# S3_LED_MAT_FPGA_POWER.net
KiCad netlist of a schematic drawn in Altium Designer
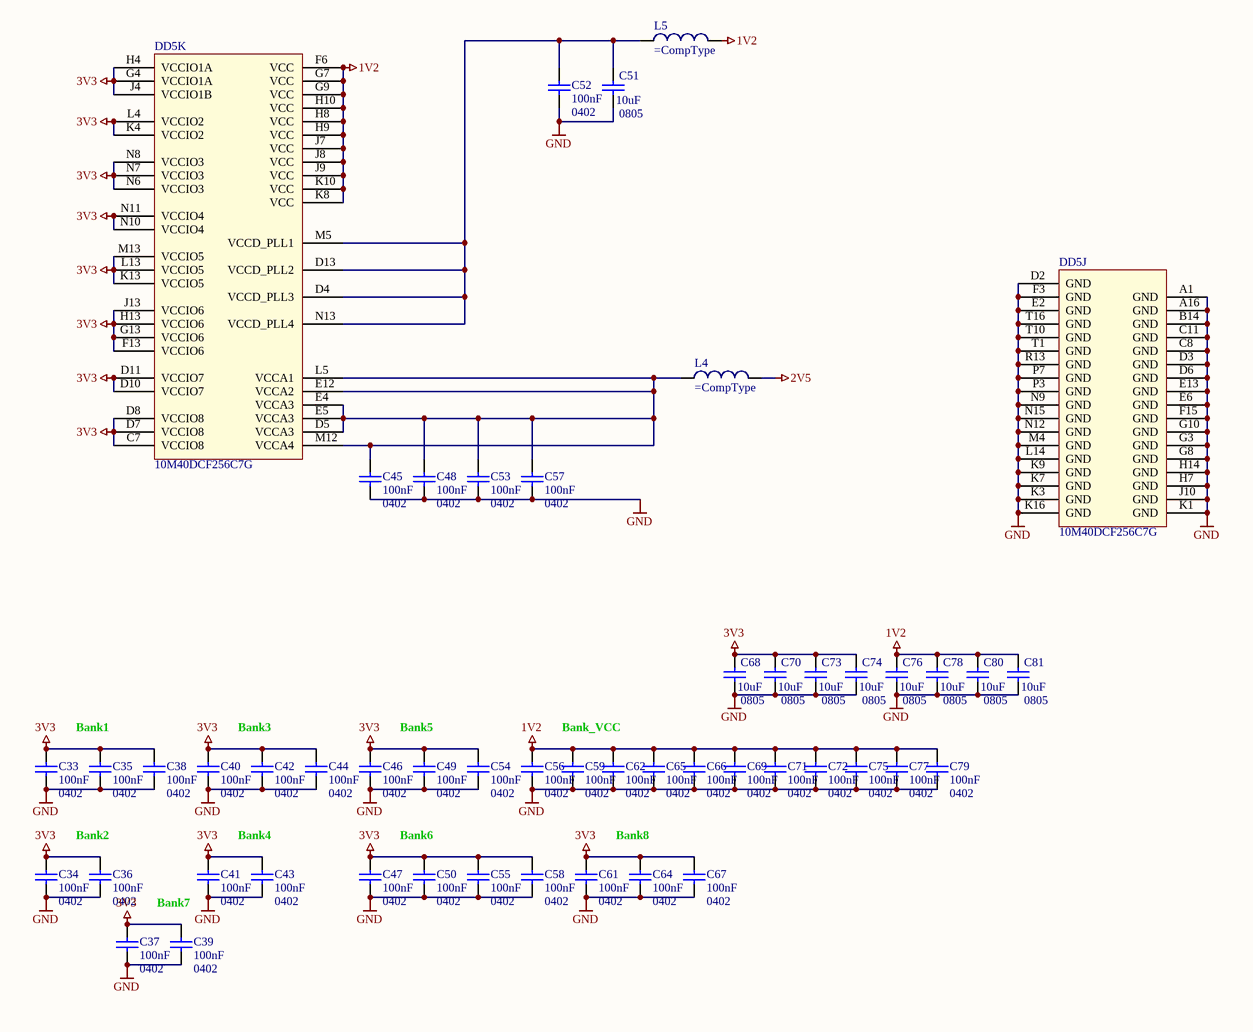
[diagram p0: S3_LED_MAT_FPGA_POWER.SchDoc]

(export (version "E")
  (design (tool "Eeschema 10.0.6"))
  (components
    (comp (ref "C33")
      (value "100nF")
      (footprint "CAPC1005L")
      (description "Capacitor ceramic")
      (fields
        (field (name "MANUFACTURER") "SAMSUNG")
        (field (name "MANUFACTURER PART NUMBER") "CL05B104KO5NNNC")
        (field (name "PACKAGE") "0402")
      )
      (libsource (lib "LED_MAT_3") (part "100nF / 0402 / X7R / 16V"))
    )
    (comp (ref "C34")
      (value "100nF")
      (footprint "CAPC1005L")
      (description "Capacitor ceramic")
      (fields
        (field (name "MANUFACTURER") "SAMSUNG")
        (field (name "MANUFACTURER PART NUMBER") "CL05B104KO5NNNC")
        (field (name "PACKAGE") "0402")
      )
      (libsource (lib "LED_MAT_3") (part "100nF / 0402 / X7R / 16V"))
    )
    (comp (ref "C35")
      (value "100nF")
      (footprint "CAPC1005L")
      (description "Capacitor ceramic")
      (fields
        (field (name "MANUFACTURER") "SAMSUNG")
        (field (name "MANUFACTURER PART NUMBER") "CL05B104KO5NNNC")
        (field (name "PACKAGE") "0402")
      )
      (libsource (lib "LED_MAT_3") (part "100nF / 0402 / X7R / 16V"))
    )
    (comp (ref "C36")
      (value "100nF")
      (footprint "CAPC1005L")
      (description "Capacitor ceramic")
      (fields
        (field (name "MANUFACTURER") "SAMSUNG")
        (field (name "MANUFACTURER PART NUMBER") "CL05B104KO5NNNC")
        (field (name "PACKAGE") "0402")
      )
      (libsource (lib "LED_MAT_3") (part "100nF / 0402 / X7R / 16V"))
    )
    (comp (ref "C37")
      (value "100nF")
      (footprint "CAPC1005L")
      (description "Capacitor ceramic")
      (fields
        (field (name "MANUFACTURER") "SAMSUNG")
        (field (name "MANUFACTURER PART NUMBER") "CL05B104KO5NNNC")
        (field (name "PACKAGE") "0402")
      )
      (libsource (lib "LED_MAT_3") (part "100nF / 0402 / X7R / 16V"))
    )
    (comp (ref "C38")
      (value "100nF")
      (footprint "CAPC1005L")
      (description "Capacitor ceramic")
      (fields
        (field (name "MANUFACTURER") "SAMSUNG")
        (field (name "MANUFACTURER PART NUMBER") "CL05B104KO5NNNC")
        (field (name "PACKAGE") "0402")
      )
      (libsource (lib "LED_MAT_3") (part "100nF / 0402 / X7R / 16V"))
    )
    (comp (ref "C39")
      (value "100nF")
      (footprint "CAPC1005L")
      (description "Capacitor ceramic")
      (fields
        (field (name "MANUFACTURER") "SAMSUNG")
        (field (name "MANUFACTURER PART NUMBER") "CL05B104KO5NNNC")
        (field (name "PACKAGE") "0402")
      )
      (libsource (lib "LED_MAT_3") (part "100nF / 0402 / X7R / 16V"))
    )
    (comp (ref "C40")
      (value "100nF")
      (footprint "CAPC1005L")
      (description "Capacitor ceramic")
      (fields
        (field (name "MANUFACTURER") "SAMSUNG")
        (field (name "MANUFACTURER PART NUMBER") "CL05B104KO5NNNC")
        (field (name "PACKAGE") "0402")
      )
      (libsource (lib "LED_MAT_3") (part "100nF / 0402 / X7R / 16V"))
    )
    (comp (ref "C41")
      (value "100nF")
      (footprint "CAPC1005L")
      (description "Capacitor ceramic")
      (fields
        (field (name "MANUFACTURER") "SAMSUNG")
        (field (name "MANUFACTURER PART NUMBER") "CL05B104KO5NNNC")
        (field (name "PACKAGE") "0402")
      )
      (libsource (lib "LED_MAT_3") (part "100nF / 0402 / X7R / 16V"))
    )
    (comp (ref "C42")
      (value "100nF")
      (footprint "CAPC1005L")
      (description "Capacitor ceramic")
      (fields
        (field (name "MANUFACTURER") "SAMSUNG")
        (field (name "MANUFACTURER PART NUMBER") "CL05B104KO5NNNC")
        (field (name "PACKAGE") "0402")
      )
      (libsource (lib "LED_MAT_3") (part "100nF / 0402 / X7R / 16V"))
    )
    (comp (ref "C43")
      (value "100nF")
      (footprint "CAPC1005L")
      (description "Capacitor ceramic")
      (fields
        (field (name "MANUFACTURER") "SAMSUNG")
        (field (name "MANUFACTURER PART NUMBER") "CL05B104KO5NNNC")
        (field (name "PACKAGE") "0402")
      )
      (libsource (lib "LED_MAT_3") (part "100nF / 0402 / X7R / 16V"))
    )
    (comp (ref "C44")
      (value "100nF")
      (footprint "CAPC1005L")
      (description "Capacitor ceramic")
      (fields
        (field (name "MANUFACTURER") "SAMSUNG")
        (field (name "MANUFACTURER PART NUMBER") "CL05B104KO5NNNC")
        (field (name "PACKAGE") "0402")
      )
      (libsource (lib "LED_MAT_3") (part "100nF / 0402 / X7R / 16V"))
    )
    (comp (ref "C45")
      (value "100nF")
      (footprint "CAPC1005L")
      (description "Capacitor ceramic")
      (fields
        (field (name "MANUFACTURER") "SAMSUNG")
        (field (name "MANUFACTURER PART NUMBER") "CL05B104KO5NNNC")
        (field (name "PACKAGE") "0402")
      )
      (libsource (lib "LED_MAT_3") (part "100nF / 0402 / X7R / 16V"))
    )
    (comp (ref "C46")
      (value "100nF")
      (footprint "CAPC1005L")
      (description "Capacitor ceramic")
      (fields
        (field (name "MANUFACTURER") "SAMSUNG")
        (field (name "MANUFACTURER PART NUMBER") "CL05B104KO5NNNC")
        (field (name "PACKAGE") "0402")
      )
      (libsource (lib "LED_MAT_3") (part "100nF / 0402 / X7R / 16V"))
    )
    (comp (ref "C47")
      (value "100nF")
      (footprint "CAPC1005L")
      (description "Capacitor ceramic")
      (fields
        (field (name "MANUFACTURER") "SAMSUNG")
        (field (name "MANUFACTURER PART NUMBER") "CL05B104KO5NNNC")
        (field (name "PACKAGE") "0402")
      )
      (libsource (lib "LED_MAT_3") (part "100nF / 0402 / X7R / 16V"))
    )
    (comp (ref "C48")
      (value "100nF")
      (footprint "CAPC1005L")
      (description "Capacitor ceramic")
      (fields
        (field (name "MANUFACTURER") "SAMSUNG")
        (field (name "MANUFACTURER PART NUMBER") "CL05B104KO5NNNC")
        (field (name "PACKAGE") "0402")
      )
      (libsource (lib "LED_MAT_3") (part "100nF / 0402 / X7R / 16V"))
    )
    (comp (ref "C49")
      (value "100nF")
      (footprint "CAPC1005L")
      (description "Capacitor ceramic")
      (fields
        (field (name "MANUFACTURER") "SAMSUNG")
        (field (name "MANUFACTURER PART NUMBER") "CL05B104KO5NNNC")
        (field (name "PACKAGE") "0402")
      )
      (libsource (lib "LED_MAT_3") (part "100nF / 0402 / X7R / 16V"))
    )
    (comp (ref "C50")
      (value "100nF")
      (footprint "CAPC1005L")
      (description "Capacitor ceramic")
      (fields
        (field (name "MANUFACTURER") "SAMSUNG")
        (field (name "MANUFACTURER PART NUMBER") "CL05B104KO5NNNC")
        (field (name "PACKAGE") "0402")
      )
      (libsource (lib "LED_MAT_3") (part "100nF / 0402 / X7R / 16V"))
    )
    (comp (ref "C51")
      (value "10uF")
      (footprint "CAPC2012L")
      (description "Capacitor ceramic")
      (fields
        (field (name "PACKAGE") "0805")
        (field (name "VOLTAGE") "10V")
        (field (name "Comment") "10uF / 0805 /  X5R / 10V")
      )
      (libsource (lib "LED_MAT_3") (part "10uF / 0805 /  X5R / 10V"))
    )
    (comp (ref "C52")
      (value "100nF")
      (footprint "CAPC1005L")
      (description "Capacitor ceramic")
      (fields
        (field (name "MANUFACTURER") "SAMSUNG")
        (field (name "MANUFACTURER PART NUMBER") "CL05B104KO5NNNC")
        (field (name "PACKAGE") "0402")
      )
      (libsource (lib "LED_MAT_3") (part "100nF / 0402 / X7R / 16V"))
    )
    (comp (ref "C53")
      (value "100nF")
      (footprint "CAPC1005L")
      (description "Capacitor ceramic")
      (fields
        (field (name "MANUFACTURER") "SAMSUNG")
        (field (name "MANUFACTURER PART NUMBER") "CL05B104KO5NNNC")
        (field (name "PACKAGE") "0402")
      )
      (libsource (lib "LED_MAT_3") (part "100nF / 0402 / X7R / 16V"))
    )
    (comp (ref "C54")
      (value "100nF")
      (footprint "CAPC1005L")
      (description "Capacitor ceramic")
      (fields
        (field (name "MANUFACTURER") "SAMSUNG")
        (field (name "MANUFACTURER PART NUMBER") "CL05B104KO5NNNC")
        (field (name "PACKAGE") "0402")
      )
      (libsource (lib "LED_MAT_3") (part "100nF / 0402 / X7R / 16V"))
    )
    (comp (ref "C55")
      (value "100nF")
      (footprint "CAPC1005L")
      (description "Capacitor ceramic")
      (fields
        (field (name "MANUFACTURER") "SAMSUNG")
        (field (name "MANUFACTURER PART NUMBER") "CL05B104KO5NNNC")
        (field (name "PACKAGE") "0402")
      )
      (libsource (lib "LED_MAT_3") (part "100nF / 0402 / X7R / 16V"))
    )
    (comp (ref "C56")
      (value "100nF")
      (footprint "CAPC1005L")
      (description "Capacitor ceramic")
      (fields
        (field (name "MANUFACTURER") "SAMSUNG")
        (field (name "MANUFACTURER PART NUMBER") "CL05B104KO5NNNC")
        (field (name "PACKAGE") "0402")
      )
      (libsource (lib "LED_MAT_3") (part "100nF / 0402 / X7R / 16V"))
    )
    (comp (ref "C57")
      (value "100nF")
      (footprint "CAPC1005L")
      (description "Capacitor ceramic")
      (fields
        (field (name "MANUFACTURER") "SAMSUNG")
        (field (name "MANUFACTURER PART NUMBER") "CL05B104KO5NNNC")
        (field (name "PACKAGE") "0402")
      )
      (libsource (lib "LED_MAT_3") (part "100nF / 0402 / X7R / 16V"))
    )
    (comp (ref "C58")
      (value "100nF")
      (footprint "CAPC1005L")
      (description "Capacitor ceramic")
      (fields
        (field (name "MANUFACTURER") "SAMSUNG")
        (field (name "MANUFACTURER PART NUMBER") "CL05B104KO5NNNC")
        (field (name "PACKAGE") "0402")
      )
      (libsource (lib "LED_MAT_3") (part "100nF / 0402 / X7R / 16V"))
    )
    (comp (ref "C59")
      (value "100nF")
      (footprint "CAPC1005L")
      (description "Capacitor ceramic")
      (fields
        (field (name "MANUFACTURER") "SAMSUNG")
        (field (name "MANUFACTURER PART NUMBER") "CL05B104KO5NNNC")
        (field (name "PACKAGE") "0402")
      )
      (libsource (lib "LED_MAT_3") (part "100nF / 0402 / X7R / 16V"))
    )
    (comp (ref "C61")
      (value "100nF")
      (footprint "CAPC1005L")
      (description "Capacitor ceramic")
      (fields
        (field (name "MANUFACTURER") "SAMSUNG")
        (field (name "MANUFACTURER PART NUMBER") "CL05B104KO5NNNC")
        (field (name "PACKAGE") "0402")
      )
      (libsource (lib "LED_MAT_3") (part "100nF / 0402 / X7R / 16V"))
    )
    (comp (ref "C62")
      (value "100nF")
      (footprint "CAPC1005L")
      (description "Capacitor ceramic")
      (fields
        (field (name "MANUFACTURER") "SAMSUNG")
        (field (name "MANUFACTURER PART NUMBER") "CL05B104KO5NNNC")
        (field (name "PACKAGE") "0402")
      )
      (libsource (lib "LED_MAT_3") (part "100nF / 0402 / X7R / 16V"))
    )
    (comp (ref "C64")
      (value "100nF")
      (footprint "CAPC1005L")
      (description "Capacitor ceramic")
      (fields
        (field (name "MANUFACTURER") "SAMSUNG")
        (field (name "MANUFACTURER PART NUMBER") "CL05B104KO5NNNC")
        (field (name "PACKAGE") "0402")
      )
      (libsource (lib "LED_MAT_3") (part "100nF / 0402 / X7R / 16V"))
    )
    (comp (ref "C65")
      (value "100nF")
      (footprint "CAPC1005L")
      (description "Capacitor ceramic")
      (fields
        (field (name "MANUFACTURER") "SAMSUNG")
        (field (name "MANUFACTURER PART NUMBER") "CL05B104KO5NNNC")
        (field (name "PACKAGE") "0402")
      )
      (libsource (lib "LED_MAT_3") (part "100nF / 0402 / X7R / 16V"))
    )
    (comp (ref "C66")
      (value "100nF")
      (footprint "CAPC1005L")
      (description "Capacitor ceramic")
      (fields
        (field (name "MANUFACTURER") "SAMSUNG")
        (field (name "MANUFACTURER PART NUMBER") "CL05B104KO5NNNC")
        (field (name "PACKAGE") "0402")
      )
      (libsource (lib "LED_MAT_3") (part "100nF / 0402 / X7R / 16V"))
    )
    (comp (ref "C67")
      (value "100nF")
      (footprint "CAPC1005L")
      (description "Capacitor ceramic")
      (fields
        (field (name "MANUFACTURER") "SAMSUNG")
        (field (name "MANUFACTURER PART NUMBER") "CL05B104KO5NNNC")
        (field (name "PACKAGE") "0402")
      )
      (libsource (lib "LED_MAT_3") (part "100nF / 0402 / X7R / 16V"))
    )
    (comp (ref "C68")
      (value "10uF")
      (footprint "CAPC2012L")
      (description "Capacitor ceramic")
      (fields
        (field (name "PACKAGE") "0805")
        (field (name "VOLTAGE") "10V")
        (field (name "Comment") "10uF / 0805 /  X5R / 10V")
      )
      (libsource (lib "LED_MAT_3") (part "10uF / 0805 /  X5R / 10V"))
    )
    (comp (ref "C69")
      (value "100nF")
      (footprint "CAPC1005L")
      (description "Capacitor ceramic")
      (fields
        (field (name "MANUFACTURER") "SAMSUNG")
        (field (name "MANUFACTURER PART NUMBER") "CL05B104KO5NNNC")
        (field (name "PACKAGE") "0402")
      )
      (libsource (lib "LED_MAT_3") (part "100nF / 0402 / X7R / 16V"))
    )
    (comp (ref "C70")
      (value "10uF")
      (footprint "CAPC2012L")
      (description "Capacitor ceramic")
      (fields
        (field (name "PACKAGE") "0805")
        (field (name "VOLTAGE") "10V")
        (field (name "Comment") "10uF / 0805 /  X5R / 10V")
      )
      (libsource (lib "LED_MAT_3") (part "10uF / 0805 /  X5R / 10V"))
    )
    (comp (ref "C71")
      (value "100nF")
      (footprint "CAPC1005L")
      (description "Capacitor ceramic")
      (fields
        (field (name "MANUFACTURER") "SAMSUNG")
        (field (name "MANUFACTURER PART NUMBER") "CL05B104KO5NNNC")
        (field (name "PACKAGE") "0402")
      )
      (libsource (lib "LED_MAT_3") (part "100nF / 0402 / X7R / 16V"))
    )
    (comp (ref "C72")
      (value "100nF")
      (footprint "CAPC1005L")
      (description "Capacitor ceramic")
      (fields
        (field (name "MANUFACTURER") "SAMSUNG")
        (field (name "MANUFACTURER PART NUMBER") "CL05B104KO5NNNC")
        (field (name "PACKAGE") "0402")
      )
      (libsource (lib "LED_MAT_3") (part "100nF / 0402 / X7R / 16V"))
    )
    (comp (ref "C73")
      (value "10uF")
      (footprint "CAPC2012L")
      (description "Capacitor ceramic")
      (fields
        (field (name "PACKAGE") "0805")
        (field (name "VOLTAGE") "10V")
        (field (name "Comment") "10uF / 0805 /  X5R / 10V")
      )
      (libsource (lib "LED_MAT_3") (part "10uF / 0805 /  X5R / 10V"))
    )
    (comp (ref "C74")
      (value "10uF")
      (footprint "CAPC2012L")
      (description "Capacitor ceramic")
      (fields
        (field (name "PACKAGE") "0805")
        (field (name "VOLTAGE") "10V")
        (field (name "Comment") "10uF / 0805 /  X5R / 10V")
      )
      (libsource (lib "LED_MAT_3") (part "10uF / 0805 /  X5R / 10V"))
    )
    (comp (ref "C75")
      (value "100nF")
      (footprint "CAPC1005L")
      (description "Capacitor ceramic")
      (fields
        (field (name "MANUFACTURER") "SAMSUNG")
        (field (name "MANUFACTURER PART NUMBER") "CL05B104KO5NNNC")
        (field (name "PACKAGE") "0402")
      )
      (libsource (lib "LED_MAT_3") (part "100nF / 0402 / X7R / 16V"))
    )
    (comp (ref "C76")
      (value "10uF")
      (footprint "CAPC2012L")
      (description "Capacitor ceramic")
      (fields
        (field (name "PACKAGE") "0805")
        (field (name "VOLTAGE") "10V")
        (field (name "Comment") "10uF / 0805 /  X5R / 10V")
      )
      (libsource (lib "LED_MAT_3") (part "10uF / 0805 /  X5R / 10V"))
    )
    (comp (ref "C77")
      (value "100nF")
      (footprint "CAPC1005L")
      (description "Capacitor ceramic")
      (fields
        (field (name "MANUFACTURER") "SAMSUNG")
        (field (name "MANUFACTURER PART NUMBER") "CL05B104KO5NNNC")
        (field (name "PACKAGE") "0402")
      )
      (libsource (lib "LED_MAT_3") (part "100nF / 0402 / X7R / 16V"))
    )
    (comp (ref "C78")
      (value "10uF")
      (footprint "CAPC2012L")
      (description "Capacitor ceramic")
      (fields
        (field (name "PACKAGE") "0805")
        (field (name "VOLTAGE") "10V")
        (field (name "Comment") "10uF / 0805 /  X5R / 10V")
      )
      (libsource (lib "LED_MAT_3") (part "10uF / 0805 /  X5R / 10V"))
    )
    (comp (ref "C79")
      (value "100nF")
      (footprint "CAPC1005L")
      (description "Capacitor ceramic")
      (fields
        (field (name "MANUFACTURER") "SAMSUNG")
        (field (name "MANUFACTURER PART NUMBER") "CL05B104KO5NNNC")
        (field (name "PACKAGE") "0402")
      )
      (libsource (lib "LED_MAT_3") (part "100nF / 0402 / X7R / 16V"))
    )
    (comp (ref "C80")
      (value "10uF")
      (footprint "CAPC2012L")
      (description "Capacitor ceramic")
      (fields
        (field (name "PACKAGE") "0805")
        (field (name "VOLTAGE") "10V")
        (field (name "Comment") "10uF / 0805 /  X5R / 10V")
      )
      (libsource (lib "LED_MAT_3") (part "10uF / 0805 /  X5R / 10V"))
    )
    (comp (ref "C81")
      (value "10uF")
      (footprint "CAPC2012L")
      (description "Capacitor ceramic")
      (fields
        (field (name "PACKAGE") "0805")
        (field (name "VOLTAGE") "10V")
        (field (name "Comment") "10uF / 0805 /  X5R / 10V")
      )
      (libsource (lib "LED_MAT_3") (part "10uF / 0805 /  X5R / 10V"))
    )
    (comp (ref "DD5")
      (value "10M40DCF256C7G")
      (footprint "BGA100P16X16-256")
      (description "FPGA")
      (fields
        (field (name "MANUFACTURER") "ALTERA")
        (field (name "MANUFACTURER PART NUMBER") "10M40DCF256C7GA")
      )
      (libsource (lib "IC") (part "10M40DCF256C7G"))
    )
    (comp (ref "L4")
      (value "~")
      (footprint "INDC2012L")
      (description "Ferrite bead")
      (fields
        (field (name "MANUFACTURER") "Murata")
        (field (name "MANUFACTURER PART NUMBER") "BLM21PG221SN1")
      )
      (libsource (lib "LED_MAT_3") (part "INDUCTOR"))
    )
    (comp (ref "L5")
      (value "~")
      (footprint "INDC2012L")
      (description "Ferrite bead")
      (fields
        (field (name "MANUFACTURER") "Murata")
        (field (name "MANUFACTURER PART NUMBER") "BLM21PG221SN1")
      )
      (libsource (lib "LED_MAT_3") (part "INDUCTOR"))
    )
  )
  (nets
    (net (code "1") (name "1V2") (class "Default")
      (node (ref "C56") (pin "2") (pinfunction "2_2") (pintype "passive"))
      (node (ref "C59") (pin "2") (pinfunction "2_2") (pintype "passive"))
      (node (ref "C62") (pin "2") (pinfunction "2_2") (pintype "passive"))
      (node (ref "C65") (pin "2") (pinfunction "2_2") (pintype "passive"))
      (node (ref "C66") (pin "2") (pinfunction "2_2") (pintype "passive"))
      (node (ref "C69") (pin "2") (pinfunction "2_2") (pintype "passive"))
      (node (ref "C71") (pin "2") (pinfunction "2_2") (pintype "passive"))
      (node (ref "C72") (pin "2") (pinfunction "2_2") (pintype "passive"))
      (node (ref "C75") (pin "2") (pinfunction "2_2") (pintype "passive"))
      (node (ref "C76") (pin "2") (pinfunction "2_2") (pintype "passive"))
      (node (ref "C77") (pin "2") (pinfunction "2_2") (pintype "passive"))
      (node (ref "C78") (pin "2") (pinfunction "2_2") (pintype "passive"))
      (node (ref "C79") (pin "2") (pinfunction "2_2") (pintype "passive"))
      (node (ref "C80") (pin "2") (pinfunction "2_2") (pintype "passive"))
      (node (ref "C81") (pin "2") (pinfunction "2_2") (pintype "passive"))
      (node (ref "DD5") (pin "F6") (pinfunction "VCC_F6") (pintype "power_in"))
      (node (ref "DD5") (pin "G7") (pinfunction "VCC_G7") (pintype "power_in"))
      (node (ref "DD5") (pin "G9") (pinfunction "VCC_G9") (pintype "power_in"))
      (node (ref "DD5") (pin "H10") (pinfunction "VCC_H10") (pintype "power_in"))
      (node (ref "DD5") (pin "H8") (pinfunction "VCC_H8") (pintype "power_in"))
      (node (ref "DD5") (pin "H9") (pinfunction "VCC_H9") (pintype "power_in"))
      (node (ref "DD5") (pin "J7") (pinfunction "VCC_J7") (pintype "power_in"))
      (node (ref "DD5") (pin "J8") (pinfunction "VCC_J8") (pintype "power_in"))
      (node (ref "DD5") (pin "J9") (pinfunction "VCC_J9") (pintype "power_in"))
      (node (ref "DD5") (pin "K10") (pinfunction "VCC_K10") (pintype "power_in"))
      (node (ref "DD5") (pin "K8") (pinfunction "VCC_K8") (pintype "power_in"))
      (node (ref "L5") (pin "2") (pinfunction "2_2") (pintype "passive"))
    )
    (net (code "2") (name "2V5") (class "Default")
      (node (ref "L4") (pin "2") (pinfunction "2_2") (pintype "passive"))
    )
    (net (code "3") (name "3V3") (class "Default")
      (node (ref "C33") (pin "2") (pinfunction "2_2") (pintype "passive"))
      (node (ref "C34") (pin "2") (pinfunction "2_2") (pintype "passive"))
      (node (ref "C35") (pin "2") (pinfunction "2_2") (pintype "passive"))
      (node (ref "C36") (pin "2") (pinfunction "2_2") (pintype "passive"))
      (node (ref "C37") (pin "2") (pinfunction "2_2") (pintype "passive"))
      (node (ref "C38") (pin "2") (pinfunction "2_2") (pintype "passive"))
      (node (ref "C39") (pin "2") (pinfunction "2_2") (pintype "passive"))
      (node (ref "C40") (pin "2") (pinfunction "2_2") (pintype "passive"))
      (node (ref "C41") (pin "2") (pinfunction "2_2") (pintype "passive"))
      (node (ref "C42") (pin "2") (pinfunction "2_2") (pintype "passive"))
      (node (ref "C43") (pin "2") (pinfunction "2_2") (pintype "passive"))
      (node (ref "C44") (pin "2") (pinfunction "2_2") (pintype "passive"))
      (node (ref "C46") (pin "2") (pinfunction "2_2") (pintype "passive"))
      (node (ref "C47") (pin "2") (pinfunction "2_2") (pintype "passive"))
      (node (ref "C49") (pin "2") (pinfunction "2_2") (pintype "passive"))
      (node (ref "C50") (pin "2") (pinfunction "2_2") (pintype "passive"))
      (node (ref "C54") (pin "2") (pinfunction "2_2") (pintype "passive"))
      (node (ref "C55") (pin "2") (pinfunction "2_2") (pintype "passive"))
      (node (ref "C58") (pin "2") (pinfunction "2_2") (pintype "passive"))
      (node (ref "C61") (pin "2") (pinfunction "2_2") (pintype "passive"))
      (node (ref "C64") (pin "2") (pinfunction "2_2") (pintype "passive"))
      (node (ref "C67") (pin "2") (pinfunction "2_2") (pintype "passive"))
      (node (ref "C68") (pin "2") (pinfunction "2_2") (pintype "passive"))
      (node (ref "C70") (pin "2") (pinfunction "2_2") (pintype "passive"))
      (node (ref "C73") (pin "2") (pinfunction "2_2") (pintype "passive"))
      (node (ref "C74") (pin "2") (pinfunction "2_2") (pintype "passive"))
      (node (ref "DD5") (pin "C7") (pinfunction "VCCIO8_C7") (pintype "power_in"))
      (node (ref "DD5") (pin "D10") (pinfunction "VCCIO7_D10") (pintype "power_in"))
      (node (ref "DD5") (pin "D11") (pinfunction "VCCIO7_D11") (pintype "power_in"))
      (node (ref "DD5") (pin "D7") (pinfunction "VCCIO8_D7") (pintype "power_in"))
      (node (ref "DD5") (pin "D8") (pinfunction "VCCIO8_D8") (pintype "power_in"))
      (node (ref "DD5") (pin "F13") (pinfunction "VCCIO6_F13") (pintype "power_in"))
      (node (ref "DD5") (pin "G13") (pinfunction "VCCIO6_G13") (pintype "power_in"))
      (node (ref "DD5") (pin "G4") (pinfunction "VCCIO1A_G4") (pintype "power_in"))
      (node (ref "DD5") (pin "H13") (pinfunction "VCCIO6_H13") (pintype "power_in"))
      (node (ref "DD5") (pin "H4") (pinfunction "VCCIO1A_H4") (pintype "power_in"))
      (node (ref "DD5") (pin "J13") (pinfunction "VCCIO6_J13") (pintype "power_in"))
      (node (ref "DD5") (pin "J4") (pinfunction "VCCIO1B_J4") (pintype "power_in"))
      (node (ref "DD5") (pin "K13") (pinfunction "VCCIO5_K13") (pintype "power_in"))
      (node (ref "DD5") (pin "K4") (pinfunction "VCCIO2_K4") (pintype "power_in"))
      (node (ref "DD5") (pin "L13") (pinfunction "VCCIO5_L13") (pintype "power_in"))
      (node (ref "DD5") (pin "L4") (pinfunction "VCCIO2_L4") (pintype "power_in"))
      (node (ref "DD5") (pin "M13") (pinfunction "VCCIO5_M13") (pintype "power_in"))
      (node (ref "DD5") (pin "N10") (pinfunction "VCCIO4_N10") (pintype "power_in"))
      (node (ref "DD5") (pin "N11") (pinfunction "VCCIO4_N11") (pintype "power_in"))
      (node (ref "DD5") (pin "N6") (pinfunction "VCCIO3_N6") (pintype "power_in"))
      (node (ref "DD5") (pin "N7") (pinfunction "VCCIO3_N7") (pintype "power_in"))
      (node (ref "DD5") (pin "N8") (pinfunction "VCCIO3_N8") (pintype "power_in"))
    )
    (net (code "4") (name "GND") (class "Default")
      (node (ref "C33") (pin "1") (pinfunction "1_1") (pintype "passive"))
      (node (ref "C34") (pin "1") (pinfunction "1_1") (pintype "passive"))
      (node (ref "C35") (pin "1") (pinfunction "1_1") (pintype "passive"))
      (node (ref "C36") (pin "1") (pinfunction "1_1") (pintype "passive"))
      (node (ref "C37") (pin "1") (pinfunction "1_1") (pintype "passive"))
      (node (ref "C38") (pin "1") (pinfunction "1_1") (pintype "passive"))
      (node (ref "C39") (pin "1") (pinfunction "1_1") (pintype "passive"))
      (node (ref "C40") (pin "1") (pinfunction "1_1") (pintype "passive"))
      (node (ref "C41") (pin "1") (pinfunction "1_1") (pintype "passive"))
      (node (ref "C42") (pin "1") (pinfunction "1_1") (pintype "passive"))
      (node (ref "C43") (pin "1") (pinfunction "1_1") (pintype "passive"))
      (node (ref "C44") (pin "1") (pinfunction "1_1") (pintype "passive"))
      (node (ref "C45") (pin "1") (pinfunction "1_1") (pintype "passive"))
      (node (ref "C46") (pin "1") (pinfunction "1_1") (pintype "passive"))
      (node (ref "C47") (pin "1") (pinfunction "1_1") (pintype "passive"))
      (node (ref "C48") (pin "1") (pinfunction "1_1") (pintype "passive"))
      (node (ref "C49") (pin "1") (pinfunction "1_1") (pintype "passive"))
      (node (ref "C50") (pin "1") (pinfunction "1_1") (pintype "passive"))
      (node (ref "C51") (pin "1") (pinfunction "1_1") (pintype "passive"))
      (node (ref "C52") (pin "1") (pinfunction "1_1") (pintype "passive"))
      (node (ref "C53") (pin "1") (pinfunction "1_1") (pintype "passive"))
      (node (ref "C54") (pin "1") (pinfunction "1_1") (pintype "passive"))
      (node (ref "C55") (pin "1") (pinfunction "1_1") (pintype "passive"))
      (node (ref "C56") (pin "1") (pinfunction "1_1") (pintype "passive"))
      (node (ref "C57") (pin "1") (pinfunction "1_1") (pintype "passive"))
      (node (ref "C58") (pin "1") (pinfunction "1_1") (pintype "passive"))
      (node (ref "C59") (pin "1") (pinfunction "1_1") (pintype "passive"))
      (node (ref "C61") (pin "1") (pinfunction "1_1") (pintype "passive"))
      (node (ref "C62") (pin "1") (pinfunction "1_1") (pintype "passive"))
      (node (ref "C64") (pin "1") (pinfunction "1_1") (pintype "passive"))
      (node (ref "C65") (pin "1") (pinfunction "1_1") (pintype "passive"))
      (node (ref "C66") (pin "1") (pinfunction "1_1") (pintype "passive"))
      (node (ref "C67") (pin "1") (pinfunction "1_1") (pintype "passive"))
      (node (ref "C68") (pin "1") (pinfunction "1_1") (pintype "passive"))
      (node (ref "C69") (pin "1") (pinfunction "1_1") (pintype "passive"))
      (node (ref "C70") (pin "1") (pinfunction "1_1") (pintype "passive"))
      (node (ref "C71") (pin "1") (pinfunction "1_1") (pintype "passive"))
      (node (ref "C72") (pin "1") (pinfunction "1_1") (pintype "passive"))
      (node (ref "C73") (pin "1") (pinfunction "1_1") (pintype "passive"))
      (node (ref "C74") (pin "1") (pinfunction "1_1") (pintype "passive"))
      (node (ref "C75") (pin "1") (pinfunction "1_1") (pintype "passive"))
      (node (ref "C76") (pin "1") (pinfunction "1_1") (pintype "passive"))
      (node (ref "C77") (pin "1") (pinfunction "1_1") (pintype "passive"))
      (node (ref "C78") (pin "1") (pinfunction "1_1") (pintype "passive"))
      (node (ref "C79") (pin "1") (pinfunction "1_1") (pintype "passive"))
      (node (ref "C80") (pin "1") (pinfunction "1_1") (pintype "passive"))
      (node (ref "C81") (pin "1") (pinfunction "1_1") (pintype "passive"))
      (node (ref "DD5") (pin "A1") (pinfunction "GND_A1") (pintype "power_in"))
      (node (ref "DD5") (pin "A16") (pinfunction "GND_A16") (pintype "power_in"))
      (node (ref "DD5") (pin "B14") (pinfunction "GND_B14") (pintype "power_in"))
      (node (ref "DD5") (pin "C11") (pinfunction "GND_C11") (pintype "power_in"))
      (node (ref "DD5") (pin "C8") (pinfunction "GND_C8") (pintype "power_in"))
      (node (ref "DD5") (pin "D2") (pinfunction "GND_D2") (pintype "power_in"))
      (node (ref "DD5") (pin "D3") (pinfunction "GND_D3") (pintype "power_in"))
      (node (ref "DD5") (pin "D6") (pinfunction "GND_D6") (pintype "power_in"))
      (node (ref "DD5") (pin "E13") (pinfunction "GND_E13") (pintype "power_in"))
      (node (ref "DD5") (pin "E2") (pinfunction "GND_E2") (pintype "power_in"))
      (node (ref "DD5") (pin "E6") (pinfunction "GND_E6") (pintype "power_in"))
      (node (ref "DD5") (pin "F15") (pinfunction "GND_F15") (pintype "power_in"))
      (node (ref "DD5") (pin "F3") (pinfunction "GND_F3") (pintype "power_in"))
      (node (ref "DD5") (pin "G10") (pinfunction "GND_G10") (pintype "power_in"))
      (node (ref "DD5") (pin "G3") (pinfunction "GND_G3") (pintype "power_in"))
      (node (ref "DD5") (pin "G8") (pinfunction "GND_G8") (pintype "power_in"))
      (node (ref "DD5") (pin "H14") (pinfunction "GND_H14") (pintype "power_in"))
      (node (ref "DD5") (pin "H7") (pinfunction "GND_H7") (pintype "power_in"))
      (node (ref "DD5") (pin "J10") (pinfunction "GND_J10") (pintype "power_in"))
      (node (ref "DD5") (pin "K1") (pinfunction "GND_K1") (pintype "power_in"))
      (node (ref "DD5") (pin "K16") (pinfunction "GND_K16") (pintype "power_in"))
      (node (ref "DD5") (pin "K3") (pinfunction "GND_K3") (pintype "power_in"))
      (node (ref "DD5") (pin "K7") (pinfunction "GND_K7") (pintype "power_in"))
      (node (ref "DD5") (pin "K9") (pinfunction "GND_K9") (pintype "power_in"))
      (node (ref "DD5") (pin "L14") (pinfunction "GND_L14") (pintype "power_in"))
      (node (ref "DD5") (pin "M4") (pinfunction "GND_M4") (pintype "power_in"))
      (node (ref "DD5") (pin "N12") (pinfunction "GND_N12") (pintype "power_in"))
      (node (ref "DD5") (pin "N15") (pinfunction "GND_N15") (pintype "power_in"))
      (node (ref "DD5") (pin "N9") (pinfunction "GND_N9") (pintype "power_in"))
      (node (ref "DD5") (pin "P3") (pinfunction "GND_P3") (pintype "power_in"))
      (node (ref "DD5") (pin "P7") (pinfunction "GND_P7") (pintype "power_in"))
      (node (ref "DD5") (pin "R13") (pinfunction "GND_R13") (pintype "power_in"))
      (node (ref "DD5") (pin "T1") (pinfunction "GND_T1") (pintype "power_in"))
      (node (ref "DD5") (pin "T10") (pinfunction "GND_T10") (pintype "power_in"))
      (node (ref "DD5") (pin "T16") (pinfunction "GND_T16") (pintype "power_in"))
    )
    (net (code "5") (name "Net-(DD5K-VCCA1)") (class "Default")
      (node (ref "C45") (pin "2") (pinfunction "2_2") (pintype "passive"))
      (node (ref "C48") (pin "2") (pinfunction "2_2") (pintype "passive"))
      (node (ref "C53") (pin "2") (pinfunction "2_2") (pintype "passive"))
      (node (ref "C57") (pin "2") (pinfunction "2_2") (pintype "passive"))
      (node (ref "DD5") (pin "D5") (pinfunction "VCCA3_D5") (pintype "power_in"))
      (node (ref "DD5") (pin "E12") (pinfunction "VCCA2_E12") (pintype "power_in"))
      (node (ref "DD5") (pin "E4") (pinfunction "VCCA3_E4") (pintype "power_in"))
      (node (ref "DD5") (pin "E5") (pinfunction "VCCA3_E5") (pintype "power_in"))
      (node (ref "DD5") (pin "L5") (pinfunction "VCCA1_L5") (pintype "power_in"))
      (node (ref "DD5") (pin "M12") (pinfunction "VCCA4_M12") (pintype "power_in"))
      (node (ref "L4") (pin "1") (pinfunction "1_1") (pintype "passive"))
    )
    (net (code "6") (name "Net-(DD5K-VCCD_PLL1)") (class "Default")
      (node (ref "C51") (pin "2") (pinfunction "2_2") (pintype "passive"))
      (node (ref "C52") (pin "2") (pinfunction "2_2") (pintype "passive"))
      (node (ref "DD5") (pin "D13") (pinfunction "VCCD_PLL2_D13") (pintype "power_in"))
      (node (ref "DD5") (pin "D4") (pinfunction "VCCD_PLL3_D4") (pintype "power_in"))
      (node (ref "DD5") (pin "M5") (pinfunction "VCCD_PLL1_M5") (pintype "power_in"))
      (node (ref "DD5") (pin "N13") (pinfunction "VCCD_PLL4_N13") (pintype "power_in"))
      (node (ref "L5") (pin "1") (pinfunction "1_1") (pintype "passive"))
    )
  )
)
